# Top.net
KiCad netlist of a schematic drawn in Altium Designer
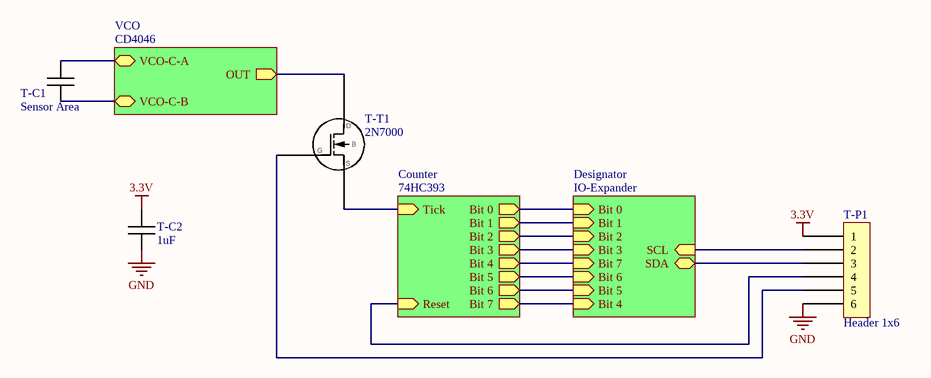
[diagram p0: Top.SchDoc]

(export (version "E")
  (design (tool "Eeschema 10.0.6"))
  (components
    (comp (ref "T-C1") (value "Sensor Area") (libsource (lib "Standard") (part "Capacitor")))
    (comp (ref "T-C2")
      (value "1uF")
      (footprint "C 0805 / 2012")
      (libsource (lib "Standard") (part "Capacitor"))
    )
    (comp (ref "T-P1")
      (value "Header 1x6")
      (footprint "Header 1x6")
      (libsource (lib "Headers") (part "Header 1x6"))
    )
    (comp (ref "T-T1")
      (value "2N7000")
      (footprint "SOT-23-3")
      (description "N-FET")
      (libsource (lib "ICs") (part "2N7000"))
    )
  )
  (nets
    (net (code "9") (name "/OUT") (class "Default")
      (node (ref "T-T1") (pin "3") (pinfunction "3_3") (pintype "passive"))
    )
    (net (code "10") (name "/Reset") (class "Default")
      (node (ref "T-P1") (pin "4") (pinfunction "4_4") (pintype "passive"))
    )
    (net (code "11") (name "/SCL") (class "Default")
      (node (ref "T-P1") (pin "2") (pinfunction "2_2") (pintype "passive"))
    )
    (net (code "12") (name "/SDA") (class "Default")
      (node (ref "T-P1") (pin "3") (pinfunction "3_3") (pintype "passive"))
    )
    (net (code "13") (name "/Tick") (class "Default")
      (node (ref "T-T1") (pin "2") (pinfunction "2_2") (pintype "passive"))
    )
    (net (code "14") (name "/VCO-C-A") (class "Default")
      (node (ref "T-C1") (pin "1") (pinfunction "1_1") (pintype "passive"))
    )
    (net (code "15") (name "/VCO-C-B") (class "Default")
      (node (ref "T-C1") (pin "2") (pinfunction "1_2") (pintype "passive"))
    )
    (net (code "16") (name "3.3V") (class "Default")
      (node (ref "T-C2") (pin "1") (pinfunction "1_1") (pintype "passive"))
      (node (ref "T-P1") (pin "1") (pinfunction "1_1") (pintype "passive"))
    )
    (net (code "17") (name "GND") (class "Default")
      (node (ref "T-C2") (pin "2") (pinfunction "1_2") (pintype "passive"))
      (node (ref "T-P1") (pin "6") (pinfunction "6_6") (pintype "passive"))
    )
    (net (code "18") (name "Net-(T-P1-Pad5)") (class "Default")
      (node (ref "T-P1") (pin "5") (pinfunction "5_5") (pintype "passive"))
      (node (ref "T-T1") (pin "1") (pinfunction "1_1") (pintype "passive"))
    )
  )
)
